# lab.net
KiCad netlist of a schematic drawn in EAGLE
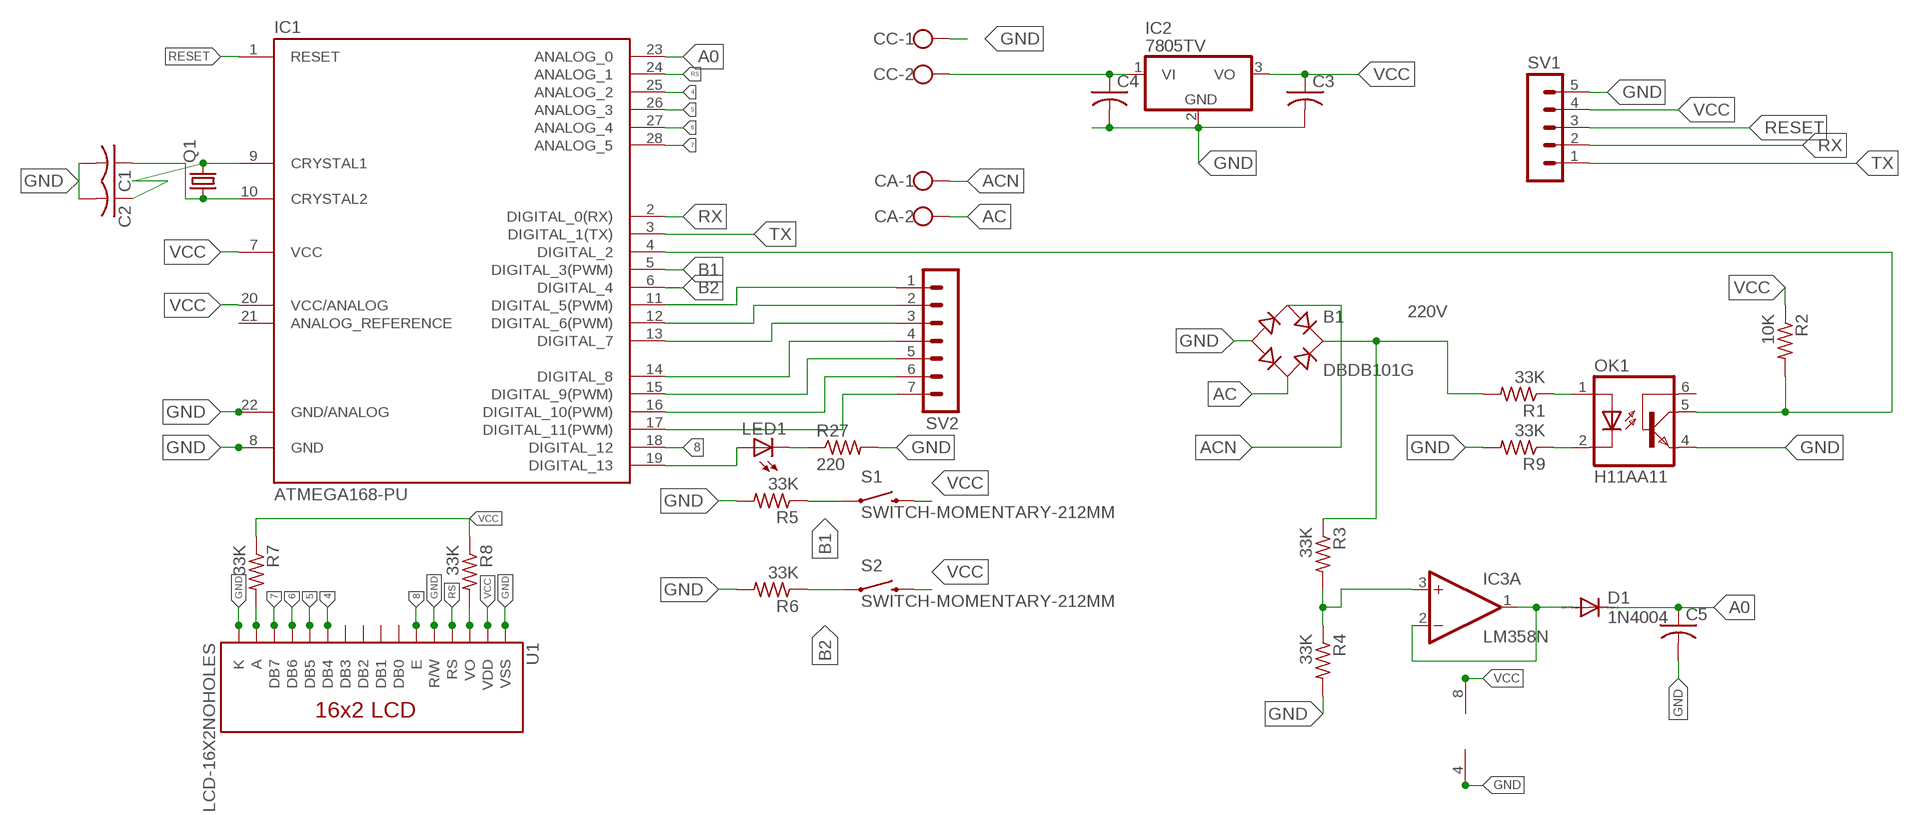
[diagram p0: schematic, sheet 1]

(export (version "E")
  (design (tool "Eeschema 10.0.6"))
  (components
    (comp (ref "B1")
      (value "DBDB101G")
      (footprint "eagle-import:DB")
      (libsource (lib "eagle-import") (part "DB?GDB101"))
    )
    (comp (ref "C1")
      (value "C-US025-025X050")
      (footprint "eagle-import:C025-025X050")
      (libsource (lib "eagle-import") (part "C-US025-025X050"))
    )
    (comp (ref "C2")
      (value "C-US025-025X050")
      (footprint "eagle-import:C025-025X050")
      (libsource (lib "eagle-import") (part "C-US025-025X050"))
    )
    (comp (ref "C3")
      (value "C-US050-025X075")
      (footprint "eagle-import:C050-025X075")
      (libsource (lib "eagle-import") (part "C-US050-025X075"))
    )
    (comp (ref "C4")
      (value "C-US050-025X075")
      (footprint "eagle-import:C050-025X075")
      (libsource (lib "eagle-import") (part "C-US050-025X075"))
    )
    (comp (ref "C5")
      (value "C-US050-025X075")
      (footprint "eagle-import:C050-025X075")
      (libsource (lib "eagle-import") (part "C-US050-025X075"))
    )
    (comp (ref "CA")
      (value "W237-102")
      (footprint "eagle-import:W237-102")
      (fields (field (name "MPN") "237-102"))
      (libsource (lib "eagle-import") (part "W237-102"))
    )
    (comp (ref "CC")
      (value "W237-102")
      (footprint "eagle-import:W237-102")
      (fields (field (name "MPN") "237-102"))
      (libsource (lib "eagle-import") (part "W237-102"))
    )
    (comp (ref "D1")
      (value "1N4004")
      (footprint "eagle-import:DO41-10")
      (libsource (lib "eagle-import") (part "1N4004"))
    )
    (comp (ref "IC1")
      (value "ATMEGA168-PU")
      (footprint "eagle-import:DIL28-3")
      (libsource (lib "eagle-import") (part "ATMEGA168-PU"))
    )
    (comp (ref "IC2")
      (value "7805TV")
      (footprint "eagle-import:TO220V")
      (libsource (lib "eagle-import") (part "78TV05"))
    )
    (comp (ref "IC3")
      (value "LM358N")
      (footprint "eagle-import:DIL08")
      (libsource (lib "eagle-import") (part "LM358N"))
    )
    (comp (ref "LED1")
      (value "LED3MM")
      (footprint "eagle-import:LED3MM")
      (libsource (lib "eagle-import") (part "LED3MM"))
    )
    (comp (ref "OK1")
      (value "H11AA11")
      (footprint "eagle-import:DIL06")
      (fields (field (name "MPN") "H11A1-M"))
      (libsource (lib "eagle-import") (part "H11AA11"))
    )
    (comp (ref "Q1")
      (value "CRYSTALHC18U-V")
      (footprint "eagle-import:HC18U-V")
      (libsource (lib "eagle-import") (part "CRYSTALHC18U-V"))
    )
    (comp (ref "R1")
      (value "33K")
      (footprint "eagle-import:0207_7")
      (libsource (lib "eagle-import") (part "R-US_0207/7"))
    )
    (comp (ref "R2")
      (value "10K")
      (footprint "eagle-import:0207_7")
      (libsource (lib "eagle-import") (part "R-US_0207/7"))
    )
    (comp (ref "R3")
      (value "33K")
      (footprint "eagle-import:0207_7")
      (libsource (lib "eagle-import") (part "R-US_0207/7"))
    )
    (comp (ref "R4")
      (value "33K")
      (footprint "eagle-import:0207_7")
      (libsource (lib "eagle-import") (part "R-US_0207/7"))
    )
    (comp (ref "R5")
      (value "33K")
      (footprint "eagle-import:0207_7")
      (libsource (lib "eagle-import") (part "R-US_0207/7"))
    )
    (comp (ref "R6")
      (value "33K")
      (footprint "eagle-import:0207_7")
      (libsource (lib "eagle-import") (part "R-US_0207/7"))
    )
    (comp (ref "R7")
      (value "33K")
      (footprint "eagle-import:0207_7")
      (libsource (lib "eagle-import") (part "R-US_0207/7"))
    )
    (comp (ref "R8")
      (value "33K")
      (footprint "eagle-import:0207_7")
      (libsource (lib "eagle-import") (part "R-US_0207/7"))
    )
    (comp (ref "R9")
      (value "33K")
      (footprint "eagle-import:0207_7")
      (libsource (lib "eagle-import") (part "R-US_0207/7"))
    )
    (comp (ref "R27")
      (value "220")
      (footprint "eagle-import:0309_10")
      (libsource (lib "eagle-import") (part "rcl_R-US_0309/10"))
    )
    (comp (ref "S1")
      (value "SWITCH-MOMENTARY-212MM")
      (footprint "eagle-import:TACTILE-PTH-12MM")
      (libsource (lib "eagle-import") (part "SWITCH-MOMENTARY-212MM"))
    )
    (comp (ref "S2")
      (value "SWITCH-MOMENTARY-212MM")
      (footprint "eagle-import:TACTILE-PTH-12MM")
      (libsource (lib "eagle-import") (part "SWITCH-MOMENTARY-212MM"))
    )
    (comp (ref "SV1")
      (value "MA05-1")
      (footprint "eagle-import:MA05-1")
      (libsource (lib "eagle-import") (part "MA05-1"))
    )
    (comp (ref "SV2")
      (value "MA07-1")
      (footprint "eagle-import:MA07-1")
      (libsource (lib "eagle-import") (part "MA07-1"))
    )
    (comp (ref "U1")
      (value "LCD-16X2NOHOLES")
      (footprint "eagle-import:LCD-16X2_NOHOLES")
      (libsource (lib "eagle-import") (part "LCD-16X2NOHOLES"))
    )
  )
  (nets
    (net (code "1") (name "/220V") (class "Default")
      (node (ref "B1") (pin "+") (pinfunction "+_+") (pintype "passive"))
      (node (ref "R1") (pin "2") (pinfunction "2_2") (pintype "passive"))
      (node (ref "R3") (pin "1") (pinfunction "1_1") (pintype "passive"))
    )
    (net (code "2") (name "4") (class "Default")
      (node (ref "IC1") (pin "25") (pinfunction "ANALOG_2_25") (pintype "bidirectional"))
      (node (ref "U1") (pin "11") (pinfunction "DB4_11") (pintype "bidirectional"))
    )
    (net (code "3") (name "5") (class "Default")
      (node (ref "IC1") (pin "26") (pinfunction "ANALOG_3_26") (pintype "bidirectional"))
      (node (ref "U1") (pin "12") (pinfunction "DB5_12") (pintype "bidirectional"))
    )
    (net (code "4") (name "6") (class "Default")
      (node (ref "IC1") (pin "27") (pinfunction "ANALOG_4_27") (pintype "bidirectional"))
      (node (ref "U1") (pin "13") (pinfunction "DB6_13") (pintype "bidirectional"))
    )
    (net (code "5") (name "7") (class "Default")
      (node (ref "IC1") (pin "28") (pinfunction "ANALOG_5_28") (pintype "bidirectional"))
      (node (ref "U1") (pin "14") (pinfunction "DB7_14") (pintype "bidirectional"))
    )
    (net (code "6") (name "8") (class "Default")
      (node (ref "IC1") (pin "18") (pinfunction "DIGITAL_12_18") (pintype "bidirectional"))
      (node (ref "U1") (pin "6") (pinfunction "E_6") (pintype "input"))
    )
    (net (code "7") (name "A0") (class "Default")
      (node (ref "C5") (pin "1") (pinfunction "1_1") (pintype "passive"))
      (node (ref "D1") (pin "C") (pinfunction "C_C") (pintype "passive"))
      (node (ref "IC1") (pin "23") (pinfunction "ANALOG_0_23") (pintype "bidirectional"))
    )
    (net (code "8") (name "AC") (class "Default")
      (node (ref "B1") (pin "AC2") (pinfunction "AC2_AC2") (pintype "passive"))
      (node (ref "CA") (pin "2") (pinfunction "KL_2") (pintype "passive"))
    )
    (net (code "9") (name "ACN") (class "Default")
      (node (ref "B1") (pin "AC1") (pinfunction "AC1_AC1") (pintype "passive"))
      (node (ref "CA") (pin "1") (pinfunction "KL_1") (pintype "passive"))
    )
    (net (code "10") (name "B1") (class "Default")
      (node (ref "IC1") (pin "5") (pinfunction "DIGITAL_3(PWM)_5") (pintype "bidirectional"))
      (node (ref "R5") (pin "1") (pinfunction "1_1") (pintype "passive"))
      (node (ref "S1") (pin "1") (pinfunction "1_1") (pintype "passive"))
    )
    (net (code "11") (name "B2") (class "Default")
      (node (ref "IC1") (pin "6") (pinfunction "DIGITAL_4_6") (pintype "bidirectional"))
      (node (ref "R6") (pin "1") (pinfunction "1_1") (pintype "passive"))
      (node (ref "S2") (pin "1") (pinfunction "1_1") (pintype "passive"))
    )
    (net (code "12") (name "GND") (class "Default")
      (node (ref "B1") (pin "-") (pinfunction "-_-") (pintype "passive"))
      (node (ref "C1") (pin "2") (pinfunction "2_2") (pintype "passive"))
      (node (ref "C2") (pin "2") (pinfunction "2_2") (pintype "passive"))
      (node (ref "C3") (pin "2") (pinfunction "2_2") (pintype "passive"))
      (node (ref "C4") (pin "2") (pinfunction "2_2") (pintype "passive"))
      (node (ref "C5") (pin "2") (pinfunction "2_2") (pintype "passive"))
      (node (ref "CC") (pin "1") (pinfunction "KL_1") (pintype "passive"))
      (node (ref "IC1") (pin "22") (pinfunction "GND/ANALOG_22") (pintype "power_in"))
      (node (ref "IC1") (pin "8") (pinfunction "GND_8") (pintype "power_in"))
      (node (ref "IC2") (pin "2") (pinfunction "GND_2") (pintype "passive"))
      (node (ref "IC3") (pin "4") (pinfunction "V-_4") (pintype "power_in"))
      (node (ref "OK1") (pin "4") (pinfunction "EMI_4") (pintype "passive"))
      (node (ref "R27") (pin "2") (pinfunction "2_2") (pintype "passive"))
      (node (ref "R4") (pin "2") (pinfunction "2_2") (pintype "passive"))
      (node (ref "R5") (pin "2") (pinfunction "2_2") (pintype "passive"))
      (node (ref "R6") (pin "2") (pinfunction "2_2") (pintype "passive"))
      (node (ref "R9") (pin "2") (pinfunction "2_2") (pintype "passive"))
      (node (ref "SV1") (pin "5") (pinfunction "5_5") (pintype "passive"))
      (node (ref "U1") (pin "1") (pinfunction "VSS_1") (pintype "power_in"))
      (node (ref "U1") (pin "16") (pinfunction "K_16") (pintype "power_in"))
      (node (ref "U1") (pin "5") (pinfunction "R/W_5") (pintype "input"))
    )
    (net (code "13") (name "Net-(CCB-KL)") (class "Default")
      (node (ref "C4") (pin "1") (pinfunction "1_1") (pintype "passive"))
      (node (ref "CC") (pin "2") (pinfunction "KL_2") (pintype "passive"))
      (node (ref "IC2") (pin "1") (pinfunction "VI_1") (pintype "input"))
    )
    (net (code "14") (name "Net-(IC1-CRYSTAL1)") (class "Default")
      (node (ref "C2") (pin "1") (pinfunction "1_1") (pintype "passive"))
      (node (ref "IC1") (pin "9") (pinfunction "CRYSTAL1_9") (pintype "bidirectional"))
      (node (ref "Q1") (pin "2") (pinfunction "2_2") (pintype "passive"))
    )
    (net (code "15") (name "Net-(IC1-CRYSTAL2)") (class "Default")
      (node (ref "C1") (pin "1") (pinfunction "1_1") (pintype "passive"))
      (node (ref "IC1") (pin "10") (pinfunction "CRYSTAL2_10") (pintype "bidirectional"))
      (node (ref "Q1") (pin "1") (pinfunction "1_1") (pintype "passive"))
    )
    (net (code "16") (name "Net-(IC1-DIGITAL_2)") (class "Default")
      (node (ref "IC1") (pin "4") (pinfunction "DIGITAL_2_4") (pintype "bidirectional"))
      (node (ref "OK1") (pin "5") (pinfunction "COL_5") (pintype "passive"))
      (node (ref "R2") (pin "2") (pinfunction "2_2") (pintype "passive"))
    )
    (net (code "17") (name "Net-(IC1-DIGITAL_5(PWM))") (class "Default")
      (node (ref "IC1") (pin "11") (pinfunction "DIGITAL_5(PWM)_11") (pintype "bidirectional"))
      (node (ref "SV2") (pin "1") (pinfunction "1_1") (pintype "passive"))
    )
    (net (code "18") (name "Net-(IC1-DIGITAL_6(PWM))") (class "Default")
      (node (ref "IC1") (pin "12") (pinfunction "DIGITAL_6(PWM)_12") (pintype "bidirectional"))
      (node (ref "SV2") (pin "2") (pinfunction "2_2") (pintype "passive"))
    )
    (net (code "19") (name "Net-(IC1-DIGITAL_7)") (class "Default")
      (node (ref "IC1") (pin "13") (pinfunction "DIGITAL_7_13") (pintype "bidirectional"))
      (node (ref "SV2") (pin "3") (pinfunction "3_3") (pintype "passive"))
    )
    (net (code "20") (name "Net-(IC1-DIGITAL_8)") (class "Default")
      (node (ref "IC1") (pin "14") (pinfunction "DIGITAL_8_14") (pintype "bidirectional"))
      (node (ref "SV2") (pin "4") (pinfunction "4_4") (pintype "passive"))
    )
    (net (code "21") (name "Net-(IC1-DIGITAL_9(PWM))") (class "Default")
      (node (ref "IC1") (pin "15") (pinfunction "DIGITAL_9(PWM)_15") (pintype "bidirectional"))
      (node (ref "SV2") (pin "5") (pinfunction "5_5") (pintype "passive"))
    )
    (net (code "22") (name "Net-(IC1-DIGITAL_10(PWM))") (class "Default")
      (node (ref "IC1") (pin "16") (pinfunction "DIGITAL_10(PWM)_16") (pintype "bidirectional"))
      (node (ref "SV2") (pin "6") (pinfunction "6_6") (pintype "passive"))
    )
    (net (code "23") (name "Net-(IC1-DIGITAL_11(PWM))") (class "Default")
      (node (ref "IC1") (pin "17") (pinfunction "DIGITAL_11(PWM)_17") (pintype "bidirectional"))
      (node (ref "SV2") (pin "7") (pinfunction "7_7") (pintype "passive"))
    )
    (net (code "24") (name "Net-(IC1-DIGITAL_13)") (class "Default")
      (node (ref "IC1") (pin "19") (pinfunction "DIGITAL_13_19") (pintype "bidirectional"))
      (node (ref "LED1") (pin "A") (pinfunction "A_A") (pintype "passive"))
    )
    (net (code "25") (name "Net-(IC3A-+IN)") (class "Default")
      (node (ref "IC3") (pin "3") (pinfunction "+IN_3") (pintype "input"))
      (node (ref "R3") (pin "2") (pinfunction "2_2") (pintype "passive"))
      (node (ref "R4") (pin "1") (pinfunction "1_1") (pintype "passive"))
    )
    (net (code "26") (name "Net-(IC3A--IN)") (class "Default")
      (node (ref "D1") (pin "A") (pinfunction "A_A") (pintype "passive"))
      (node (ref "IC3") (pin "1") (pinfunction "OUT_1") (pintype "output"))
      (node (ref "IC3") (pin "2") (pinfunction "-IN_2") (pintype "input"))
    )
    (net (code "27") (name "Net-(LED1-C)") (class "Default")
      (node (ref "LED1") (pin "K") (pinfunction "C_K") (pintype "passive"))
      (node (ref "R27") (pin "1") (pinfunction "1_1") (pintype "passive"))
    )
    (net (code "28") (name "Net-(OK1-A)") (class "Default")
      (node (ref "OK1") (pin "1") (pinfunction "A_1") (pintype "passive"))
      (node (ref "R1") (pin "1") (pinfunction "1_1") (pintype "passive"))
    )
    (net (code "29") (name "Net-(OK1-C)") (class "Default")
      (node (ref "OK1") (pin "2") (pinfunction "C_2") (pintype "passive"))
      (node (ref "R9") (pin "1") (pinfunction "1_1") (pintype "passive"))
    )
    (net (code "30") (name "Net-(U1-A)") (class "Default")
      (node (ref "R7") (pin "2") (pinfunction "2_2") (pintype "passive"))
      (node (ref "U1") (pin "15") (pinfunction "A_15") (pintype "power_in"))
    )
    (net (code "31") (name "Net-(U1-VO)") (class "Default")
      (node (ref "R8") (pin "2") (pinfunction "2_2") (pintype "passive"))
      (node (ref "U1") (pin "3") (pinfunction "VO_3") (pintype "bidirectional"))
    )
    (net (code "32") (name "RESET") (class "Default")
      (node (ref "IC1") (pin "1") (pinfunction "RESET_1") (pintype "bidirectional"))
      (node (ref "SV1") (pin "3") (pinfunction "3_3") (pintype "passive"))
    )
    (net (code "33") (name "RS") (class "Default")
      (node (ref "IC1") (pin "24") (pinfunction "ANALOG_1_24") (pintype "bidirectional"))
      (node (ref "U1") (pin "4") (pinfunction "RS_4") (pintype "input"))
    )
    (net (code "34") (name "RX") (class "Default")
      (node (ref "IC1") (pin "2") (pinfunction "DIGITAL_0(RX)_2") (pintype "bidirectional"))
      (node (ref "SV1") (pin "2") (pinfunction "2_2") (pintype "passive"))
    )
    (net (code "35") (name "TX") (class "Default")
      (node (ref "IC1") (pin "3") (pinfunction "DIGITAL_1(TX)_3") (pintype "bidirectional"))
      (node (ref "SV1") (pin "1") (pinfunction "1_1") (pintype "passive"))
    )
    (net (code "36") (name "VCC") (class "Default")
      (node (ref "C3") (pin "1") (pinfunction "1_1") (pintype "passive"))
      (node (ref "IC1") (pin "20") (pinfunction "VCC/ANALOG_20") (pintype "passive"))
      (node (ref "IC1") (pin "7") (pinfunction "VCC_7") (pintype "power_in"))
      (node (ref "IC2") (pin "3") (pinfunction "VO_3") (pintype "passive"))
      (node (ref "IC3") (pin "8") (pinfunction "V+_8") (pintype "power_in"))
      (node (ref "R2") (pin "1") (pinfunction "1_1") (pintype "passive"))
      (node (ref "R7") (pin "1") (pinfunction "1_1") (pintype "passive"))
      (node (ref "R8") (pin "1") (pinfunction "1_1") (pintype "passive"))
      (node (ref "S1") (pin "3") (pinfunction "2_3") (pintype "passive"))
      (node (ref "S2") (pin "3") (pinfunction "2_3") (pintype "passive"))
      (node (ref "SV1") (pin "4") (pinfunction "4_4") (pintype "passive"))
      (node (ref "U1") (pin "2") (pinfunction "VDD_2") (pintype "power_in"))
    )
    (net (code "37") (name "unconnected-(IC1-ANALOG_REFERENCE-Pad21)") (class "Default")
      (node (ref "IC1") (pin "21") (pinfunction "ANALOG_REFERENCE_21") (pintype "passive"))
    )
    (net (code "38") (name "unconnected-(OK1-BAS-Pad6)") (class "Default")
      (node (ref "OK1") (pin "6") (pinfunction "BAS_6") (pintype "passive"))
    )
    (net (code "39") (name "unconnected-(U1-DB0-Pad7)") (class "Default")
      (node (ref "U1") (pin "7") (pinfunction "DB0_7") (pintype "bidirectional"))
    )
    (net (code "40") (name "unconnected-(U1-DB1-Pad8)") (class "Default")
      (node (ref "U1") (pin "8") (pinfunction "DB1_8") (pintype "bidirectional"))
    )
    (net (code "41") (name "unconnected-(U1-DB2-Pad9)") (class "Default")
      (node (ref "U1") (pin "9") (pinfunction "DB2_9") (pintype "bidirectional"))
    )
    (net (code "42") (name "unconnected-(U1-DB3-Pad10)") (class "Default")
      (node (ref "U1") (pin "10") (pinfunction "DB3_10") (pintype "bidirectional"))
    )
  )
)
